# OPA2333_break_out_board.net
KiCad netlist of a schematic drawn in EAGLE
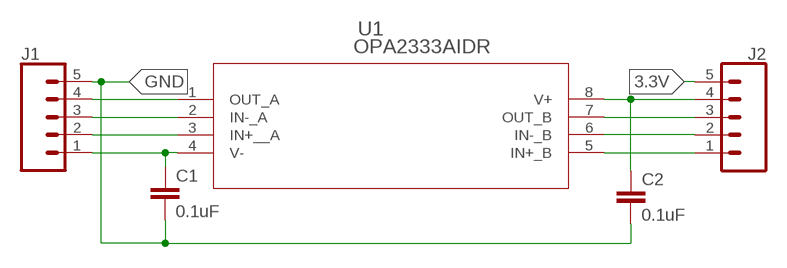
[diagram p0: schematic, sheet 1]

(export (version "E")
  (design (tool "Eeschema 10.0.6"))
  (components
    (comp (ref "C1")
      (value "0.1uF")
      (footprint "eagle-import:0603")
      (libsource (lib "eagle-import") (part "0.1UF-0603-25V-(+80/-20%)"))
    )
    (comp (ref "C2")
      (value "0.1uF")
      (footprint "eagle-import:0603")
      (libsource (lib "eagle-import") (part "0.1UF-0603-25V-(+80/-20%)"))
    )
    (comp (ref "J1")
      (value "CONN_05")
      (footprint "eagle-import:1X05")
      (libsource (lib "eagle-import") (part "CONN_05"))
    )
    (comp (ref "J2")
      (value "CONN_05")
      (footprint "eagle-import:1X05")
      (libsource (lib "eagle-import") (part "CONN_05"))
    )
    (comp (ref "U1")
      (value "OPA2333AIDR")
      (footprint "eagle-import:D8")
      (libsource (lib "eagle-import") (part "OPA2333AIDR"))
    )
  )
  (nets
    (net (code "1") (name "3.3V") (class "Default")
      (node (ref "J2") (pin "5") (pinfunction "5_5") (pintype "passive"))
    )
    (net (code "2") (name "GND") (class "Default")
      (node (ref "C1") (pin "2") (pinfunction "2_2") (pintype "passive"))
      (node (ref "C2") (pin "2") (pinfunction "2_2") (pintype "passive"))
      (node (ref "J1") (pin "5") (pinfunction "5_5") (pintype "passive"))
    )
    (net (code "3") (name "Net-(U1-IN+_B)") (class "Default")
      (node (ref "J2") (pin "1") (pinfunction "1_1") (pintype "passive"))
      (node (ref "U1") (pin "5") (pinfunction "IN+_B_5") (pintype "input"))
    )
    (net (code "4") (name "Net-(U1-IN+__A)") (class "Default")
      (node (ref "J1") (pin "2") (pinfunction "2_2") (pintype "passive"))
      (node (ref "U1") (pin "3") (pinfunction "IN+__A_3") (pintype "input"))
    )
    (net (code "5") (name "Net-(U1-IN-_A)") (class "Default")
      (node (ref "J1") (pin "3") (pinfunction "3_3") (pintype "passive"))
      (node (ref "U1") (pin "2") (pinfunction "IN-_A_2") (pintype "input"))
    )
    (net (code "6") (name "Net-(U1-IN-_B)") (class "Default")
      (node (ref "J2") (pin "2") (pinfunction "2_2") (pintype "passive"))
      (node (ref "U1") (pin "6") (pinfunction "IN-_B_6") (pintype "input"))
    )
    (net (code "7") (name "Net-(U1-OUT_A)") (class "Default")
      (node (ref "J1") (pin "4") (pinfunction "4_4") (pintype "passive"))
      (node (ref "U1") (pin "1") (pinfunction "OUT_A_1") (pintype "output"))
    )
    (net (code "8") (name "Net-(U1-OUT_B)") (class "Default")
      (node (ref "J2") (pin "3") (pinfunction "3_3") (pintype "passive"))
      (node (ref "U1") (pin "7") (pinfunction "OUT_B_7") (pintype "output"))
    )
    (net (code "9") (name "Net-(U1-V+)") (class "Default")
      (node (ref "C2") (pin "1") (pinfunction "1_1") (pintype "passive"))
      (node (ref "J2") (pin "4") (pinfunction "4_4") (pintype "passive"))
      (node (ref "U1") (pin "8") (pinfunction "V+_8") (pintype "power_in"))
    )
    (net (code "10") (name "Net-(U1-V-)") (class "Default")
      (node (ref "C1") (pin "1") (pinfunction "1_1") (pintype "passive"))
      (node (ref "J1") (pin "1") (pinfunction "1_1") (pintype "passive"))
      (node (ref "U1") (pin "4") (pinfunction "V-_4") (pintype "power_in"))
    )
  )
)
